# RF_Controller.net
KiCad netlist of a schematic drawn in Altium Designer
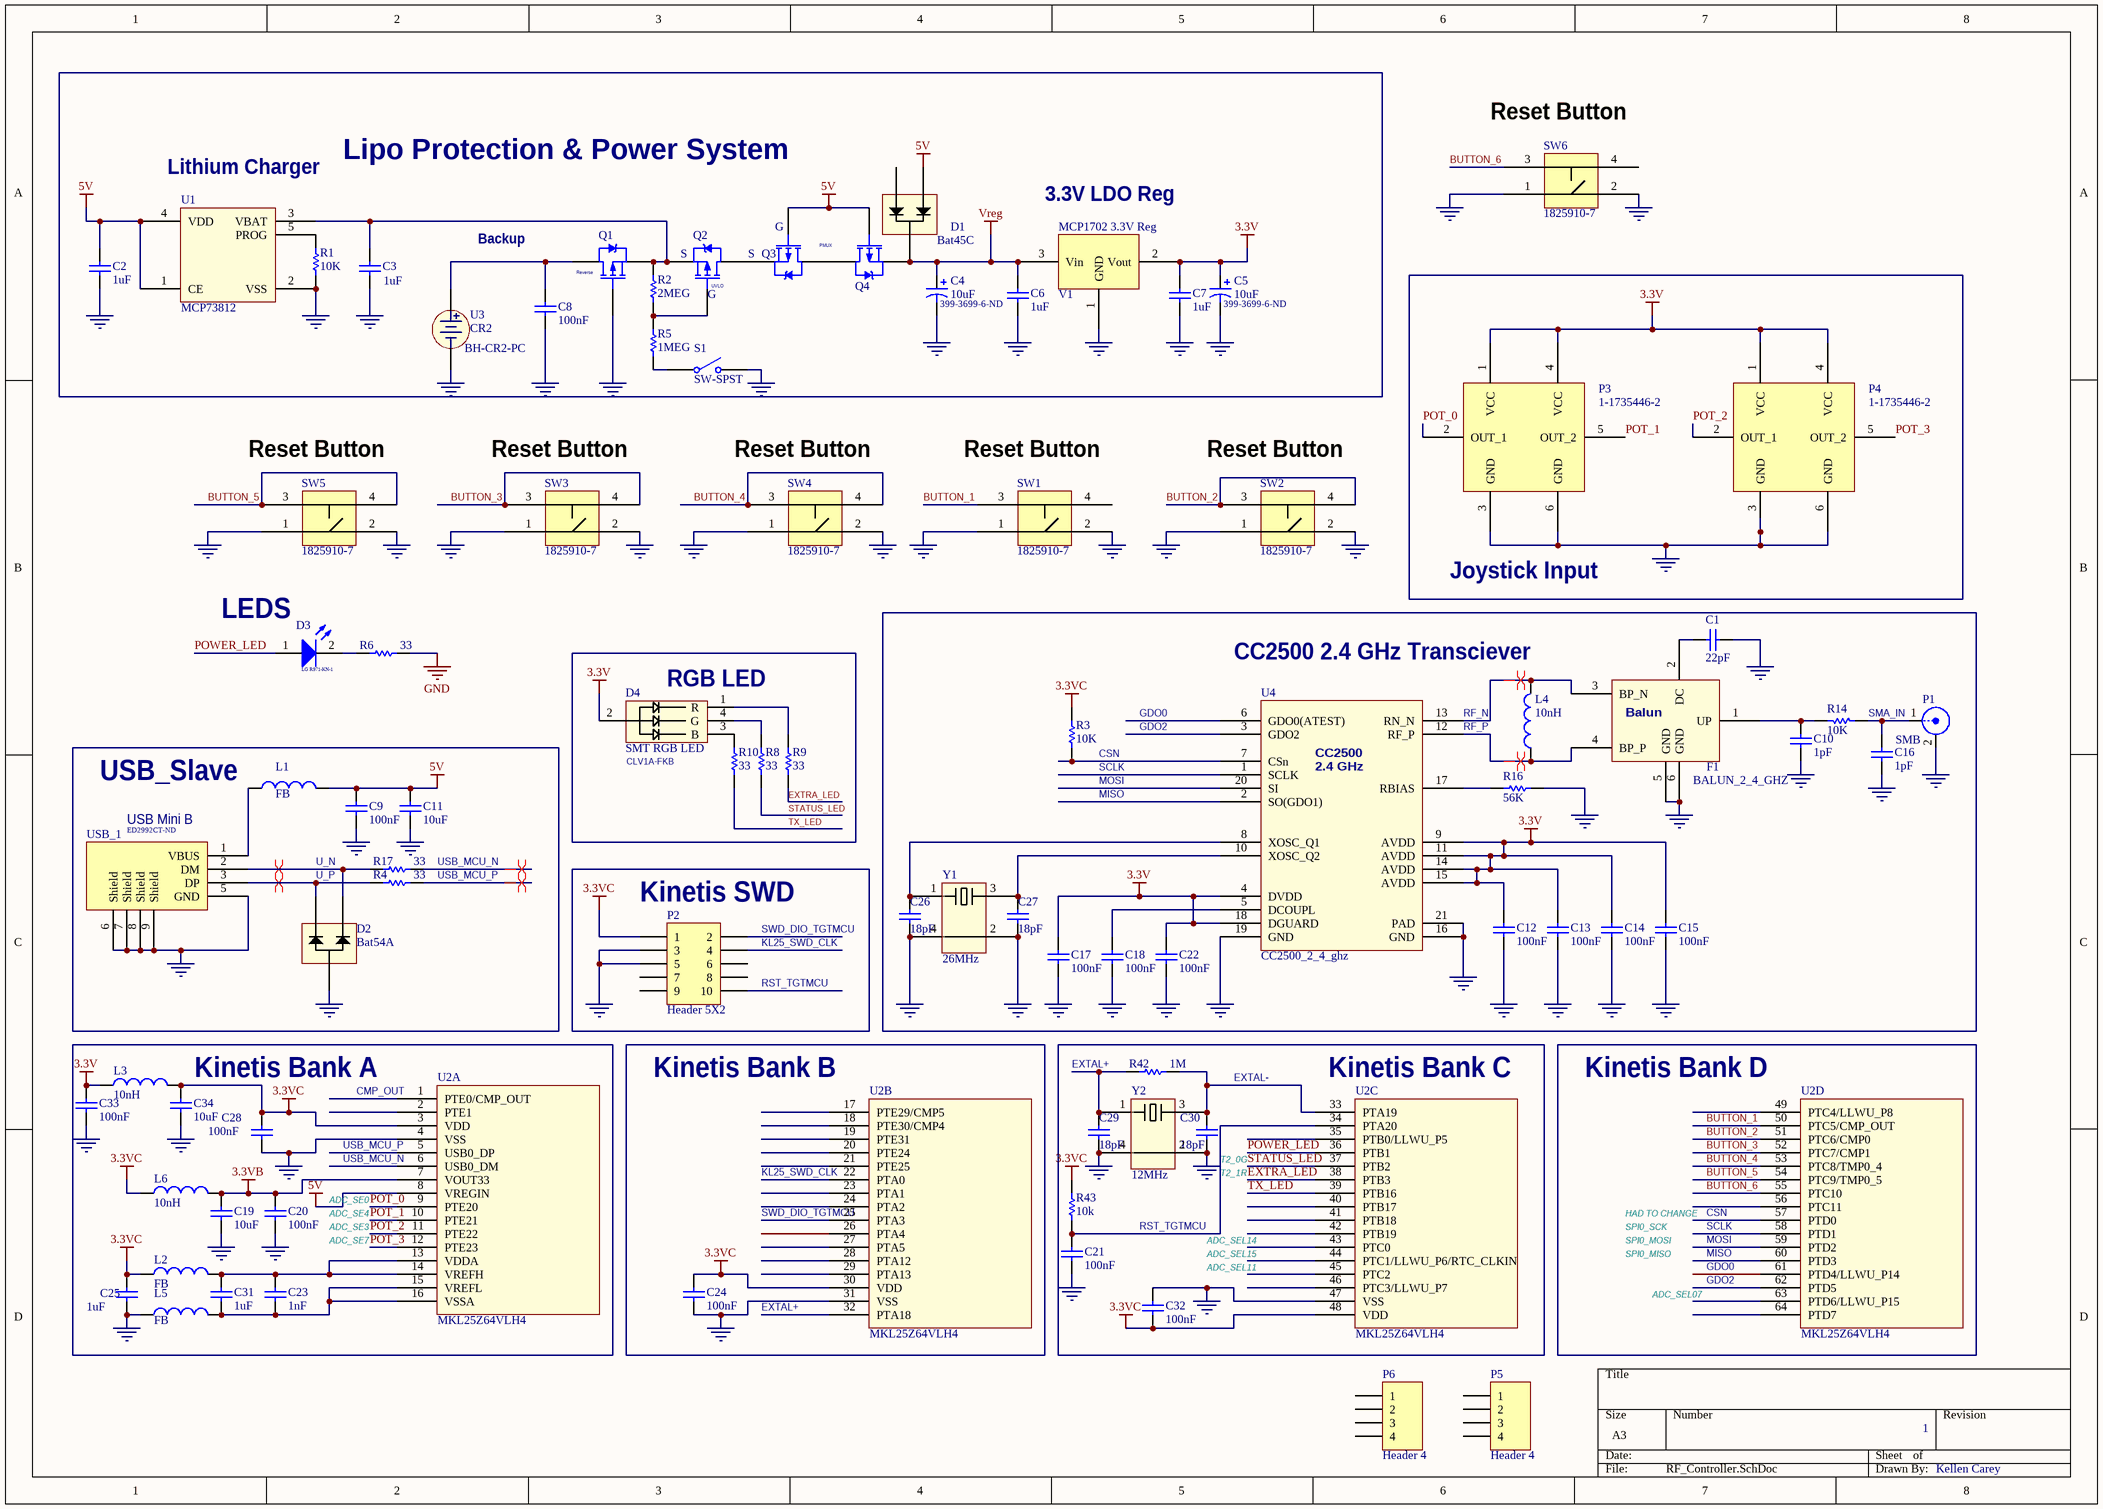
[diagram p0: RF_Controller.SchDoc]

(export (version "E")
  (design (tool "Eeschema 10.0.6"))
  (components
    (comp (ref "C1")
      (value "22pF")
      (footprint "1608[0603]C")
      (description "Capacitor (Semiconductor SIM Model)")
      (fields (field (name "Comment") "0805") (field (name "PUBLISHER") "Altium Limited"))
      (libsource (lib "Miscellaneous Devices") (part "Cap Semi"))
    )
    (comp (ref "C2")
      (value "1uF")
      (footprint "1608[0603]C")
      (description "Capacitor (Semiconductor SIM Model)")
      (fields (field (name "Comment") "0805") (field (name "PUBLISHER") "Altium Limited"))
      (libsource (lib "Miscellaneous Devices") (part "Cap Semi"))
    )
    (comp (ref "C3")
      (value "1uF")
      (footprint "1608[0603]C")
      (description "Capacitor (Semiconductor SIM Model)")
      (fields (field (name "Comment") "0805") (field (name "PUBLISHER") "Altium Limited"))
      (libsource (lib "Miscellaneous Devices") (part "Cap Semi"))
    )
    (comp (ref "C4")
      (value "10uF")
      (footprint "1206_C")
      (description "Polarized Capacitor (Radial)")
      (fields (field (name "ALTIUM_UNNAMED_1") "399-3699-6-ND") (field (name "Comment") "Cap Pol1"))
      (libsource (lib "Miscellaneous Devices") (part "Cap Pol1"))
    )
    (comp (ref "C5")
      (value "10uF")
      (footprint "1206_C")
      (description "Polarized Capacitor (Radial)")
      (fields (field (name "ALTIUM_UNNAMED_1") "399-3699-6-ND") (field (name "Comment") "Cap Pol1"))
      (libsource (lib "Miscellaneous Devices") (part "Cap Pol1"))
    )
    (comp (ref "C6")
      (value "1uF")
      (footprint "1608[0603]C")
      (description "Capacitor (Semiconductor SIM Model)")
      (fields (field (name "Comment") "0805") (field (name "PUBLISHER") "Altium Limited"))
      (libsource (lib "Miscellaneous Devices") (part "Cap Semi"))
    )
    (comp (ref "C7")
      (value "1uF")
      (footprint "1608[0603]C")
      (description "Capacitor (Semiconductor SIM Model)")
      (fields (field (name "Comment") "0805") (field (name "PUBLISHER") "Altium Limited"))
      (libsource (lib "Miscellaneous Devices") (part "Cap Semi"))
    )
    (comp (ref "C8")
      (value "100nF")
      (footprint "1608[0603]C")
      (description "Capacitor (Semiconductor SIM Model)")
      (fields (field (name "Comment") "0805") (field (name "PUBLISHER") "Altium Limited"))
      (libsource (lib "Miscellaneous Devices") (part "Cap Semi"))
    )
    (comp (ref "C9")
      (value "100nF")
      (footprint "1608[0603]C")
      (description "Capacitor (Semiconductor SIM Model)")
      (fields (field (name "Comment") "0805") (field (name "PUBLISHER") "Altium Limited"))
      (libsource (lib "Miscellaneous Devices") (part "Cap Semi"))
    )
    (comp (ref "C10")
      (value "1pF")
      (footprint "1608[0603]C")
      (description "Capacitor (Semiconductor SIM Model)")
      (fields (field (name "Comment") "0805") (field (name "PUBLISHER") "Altium Limited"))
      (libsource (lib "Miscellaneous Devices") (part "Cap Semi"))
    )
    (comp (ref "C11")
      (value "10uF")
      (footprint "C0805")
      (description "Capacitor (Semiconductor SIM Model)")
      (fields (field (name "Comment") "0805") (field (name "PUBLISHER") "Altium Limited"))
      (libsource (lib "Miscellaneous Devices") (part "Cap Semi"))
    )
    (comp (ref "C12")
      (value "100nF")
      (footprint "1608[0603]C")
      (description "Capacitor (Semiconductor SIM Model)")
      (fields (field (name "Comment") "0805") (field (name "PUBLISHER") "Altium Limited"))
      (libsource (lib "Miscellaneous Devices") (part "Cap Semi"))
    )
    (comp (ref "C13")
      (value "100nF")
      (footprint "1608[0603]C")
      (description "Capacitor (Semiconductor SIM Model)")
      (fields (field (name "Comment") "0805") (field (name "PUBLISHER") "Altium Limited"))
      (libsource (lib "Miscellaneous Devices") (part "Cap Semi"))
    )
    (comp (ref "C14")
      (value "100nF")
      (footprint "1608[0603]C")
      (description "Capacitor (Semiconductor SIM Model)")
      (fields (field (name "Comment") "0805") (field (name "PUBLISHER") "Altium Limited"))
      (libsource (lib "Miscellaneous Devices") (part "Cap Semi"))
    )
    (comp (ref "C15")
      (value "100nF")
      (footprint "1608[0603]C")
      (description "Capacitor (Semiconductor SIM Model)")
      (fields (field (name "Comment") "0805") (field (name "PUBLISHER") "Altium Limited"))
      (libsource (lib "Miscellaneous Devices") (part "Cap Semi"))
    )
    (comp (ref "C16")
      (value "1pF")
      (footprint "1608[0603]C")
      (description "Capacitor (Semiconductor SIM Model)")
      (fields (field (name "Comment") "0805") (field (name "PUBLISHER") "Altium Limited"))
      (libsource (lib "Miscellaneous Devices") (part "Cap Semi"))
    )
    (comp (ref "C17")
      (value "100nF")
      (footprint "1608[0603]C")
      (description "Capacitor (Semiconductor SIM Model)")
      (fields (field (name "Comment") "0805") (field (name "PUBLISHER") "Altium Limited"))
      (libsource (lib "Miscellaneous Devices") (part "Cap Semi"))
    )
    (comp (ref "C18")
      (value "100nF")
      (footprint "1608[0603]C")
      (description "Capacitor (Semiconductor SIM Model)")
      (fields (field (name "Comment") "0805") (field (name "PUBLISHER") "Altium Limited"))
      (libsource (lib "Miscellaneous Devices") (part "Cap Semi"))
    )
    (comp (ref "C19")
      (value "10uF")
      (footprint "C0805")
      (description "Capacitor (Semiconductor SIM Model)")
      (fields (field (name "Comment") "0805") (field (name "PUBLISHER") "Altium Limited"))
      (libsource (lib "Miscellaneous Devices") (part "Cap Semi"))
    )
    (comp (ref "C20")
      (value "100nF")
      (footprint "1608[0603]C")
      (description "Capacitor (Semiconductor SIM Model)")
      (fields (field (name "Comment") "0805") (field (name "PUBLISHER") "Altium Limited"))
      (libsource (lib "Miscellaneous Devices") (part "Cap Semi"))
    )
    (comp (ref "C21")
      (value "100nF")
      (footprint "1608[0603]C")
      (description "Capacitor (Semiconductor SIM Model)")
      (fields (field (name "Comment") "0805") (field (name "PUBLISHER") "Altium Limited"))
      (libsource (lib "Miscellaneous Devices") (part "Cap Semi"))
    )
    (comp (ref "C22")
      (value "100nF")
      (footprint "1608[0603]C")
      (description "Capacitor (Semiconductor SIM Model)")
      (fields (field (name "Comment") "0805") (field (name "PUBLISHER") "Altium Limited"))
      (libsource (lib "Miscellaneous Devices") (part "Cap Semi"))
    )
    (comp (ref "C23")
      (value "1nF")
      (footprint "1608[0603]C")
      (description "Capacitor (Semiconductor SIM Model)")
      (fields (field (name "Comment") "0805") (field (name "PUBLISHER") "Altium Limited"))
      (libsource (lib "Miscellaneous Devices") (part "Cap Semi"))
    )
    (comp (ref "C24")
      (value "100nF")
      (footprint "1608[0603]C")
      (description "Capacitor (Semiconductor SIM Model)")
      (fields (field (name "Comment") "0805") (field (name "PUBLISHER") "Altium Limited"))
      (libsource (lib "Miscellaneous Devices") (part "Cap Semi"))
    )
    (comp (ref "C25")
      (value "1uF")
      (footprint "1608[0603]C")
      (description "Capacitor (Semiconductor SIM Model)")
      (fields (field (name "Comment") "0805") (field (name "PUBLISHER") "Altium Limited"))
      (libsource (lib "Miscellaneous Devices") (part "Cap Semi"))
    )
    (comp (ref "C26")
      (value "18pF")
      (footprint "1608[0603]C")
      (description "Capacitor (Semiconductor SIM Model)")
      (fields (field (name "PART_NUMBER") "CL10C180JC8NNNC") (field (name "Comment") "0805"))
      (libsource (lib "Miscellaneous Devices") (part "Cap Semi"))
    )
    (comp (ref "C27")
      (value "18pF")
      (footprint "1608[0603]C")
      (description "Capacitor (Semiconductor SIM Model)")
      (fields (field (name "PART_NUMBER") "CL10C180JC8NNNC") (field (name "Comment") "0805"))
      (libsource (lib "Miscellaneous Devices") (part "Cap Semi"))
    )
    (comp (ref "C28")
      (value "100nF")
      (footprint "1608[0603]C")
      (description "Capacitor (Semiconductor SIM Model)")
      (fields (field (name "Comment") "0805") (field (name "PUBLISHER") "Altium Limited"))
      (libsource (lib "Miscellaneous Devices") (part "Cap Semi"))
    )
    (comp (ref "C29")
      (value "18pF")
      (footprint "1608[0603]C")
      (description "Capacitor (Semiconductor SIM Model)")
      (fields (field (name "Comment") "0805") (field (name "PUBLISHER") "Altium Limited"))
      (libsource (lib "Miscellaneous Devices") (part "Cap Semi"))
    )
    (comp (ref "C30")
      (value "18pF")
      (footprint "1608[0603]C")
      (description "Capacitor (Semiconductor SIM Model)")
      (fields (field (name "Comment") "0805") (field (name "PUBLISHER") "Altium Limited"))
      (libsource (lib "Miscellaneous Devices") (part "Cap Semi"))
    )
    (comp (ref "C31")
      (value "1uF")
      (footprint "1608[0603]C")
      (description "Capacitor (Semiconductor SIM Model)")
      (fields (field (name "Comment") "0805") (field (name "PUBLISHER") "Altium Limited"))
      (libsource (lib "Miscellaneous Devices") (part "Cap Semi"))
    )
    (comp (ref "C32")
      (value "100nF")
      (footprint "1608[0603]C")
      (description "Capacitor (Semiconductor SIM Model)")
      (fields (field (name "Comment") "0805") (field (name "PUBLISHER") "Altium Limited"))
      (libsource (lib "Miscellaneous Devices") (part "Cap Semi"))
    )
    (comp (ref "C33")
      (value "100nF")
      (footprint "1608[0603]C")
      (description "Capacitor (Semiconductor SIM Model)")
      (fields (field (name "Comment") "0805") (field (name "PUBLISHER") "Altium Limited"))
      (libsource (lib "Miscellaneous Devices") (part "Cap Semi"))
    )
    (comp (ref "C34")
      (value "10uF")
      (footprint "C0805")
      (description "Capacitor (Semiconductor SIM Model)")
      (fields (field (name "Comment") "0805") (field (name "PUBLISHER") "Altium Limited"))
      (libsource (lib "Miscellaneous Devices") (part "Cap Semi"))
    )
    (comp (ref "D1") (value "Bat45C") (footprint "SOT-23B_N") (libsource (lib "bat45") (part "Bat45C")))
    (comp (ref "D2")
      (value "Bat54A")
      (footprint "SOT-23B_N")
      (description "Bat45C")
      (libsource (lib "GSOT05CGS08") (part "Bat45C"))
    )
    (comp (ref "D3")
      (value "LG R971-KN-1")
      (footprint "6-0805_M_LED_LIB")
      (libsource (lib "Miscellaneous Devices") (part "LED3"))
    )
    (comp (ref "D4")
      (value "SMT RGB LED")
      (footprint "CLV1A-FKB_RGB_3D")
      (fields (field (name "ALTIUM_UNNAMED_1") "CLV1A-FKB"))
      (libsource (lib "RGB_LED") (part "RGB_LED_SMT"))
    )
    (comp (ref "F1")
      (value "BALUN_2_4_GHZ")
      (footprint "Balun")
      (description "2450BM15B0003")
      (libsource (lib "2450BM15B0003") (part "BALUN_2_4_GHZ"))
    )
    (comp (ref "L1")
      (value "FB")
      (footprint "1608[0603]R")
      (description "Inductor")
      (libsource (lib "Miscellaneous Devices") (part "Inductor"))
    )
    (comp (ref "L2")
      (value "FB")
      (footprint "1608[0603]R")
      (description "Inductor")
      (libsource (lib "Miscellaneous Devices") (part "Inductor"))
    )
    (comp (ref "L3")
      (value "10nH")
      (footprint "1608[0603]R")
      (description "Inductor")
      (libsource (lib "Miscellaneous Devices") (part "Inductor"))
    )
    (comp (ref "L4")
      (value "10nH")
      (footprint "1608[0603]R")
      (description "Inductor")
      (libsource (lib "Miscellaneous Devices") (part "Inductor"))
    )
    (comp (ref "L5")
      (value "FB")
      (footprint "1608[0603]R")
      (description "Inductor")
      (libsource (lib "Miscellaneous Devices") (part "Inductor"))
    )
    (comp (ref "L6")
      (value "10nH")
      (footprint "1608[0603]R")
      (description "Inductor")
      (libsource (lib "Miscellaneous Devices") (part "Inductor"))
    )
    (comp (ref "P1")
      (value "SMB")
      (footprint "SMA")
      (description "SMB Straight Connector")
      (fields (field (name "PART #") "5-1814832-1"))
      (libsource (lib "Miscellaneous Connectors") (part "SMB"))
    )
    (comp (ref "P2")
      (value "Header 5X2")
      (footprint "MHDR2X5")
      (description "Header, 5-Pin, Dual row")
      (fields (field (name "PUBLISHER") "Altium Limited"))
      (libsource (lib "Miscellaneous Connectors") (part "Header 5X2"))
    )
    (comp (ref "P3")
      (value "1-1735446-2")
      (footprint "1-1735446-2")
      (description "TE Connectivity AMP Connector")
      (libsource (lib "Joystick") (part "TE_CONN"))
    )
    (comp (ref "P4")
      (value "1-1735446-2")
      (footprint "1-1735446-2")
      (description "TE Connectivity AMP Connector")
      (libsource (lib "Joystick") (part "TE_CONN"))
    )
    (comp (ref "P5")
      (value "Header 4")
      (footprint "Joystick_Mechanical_Footprint_2")
      (description "Header, 4-Pin")
      (fields (field (name "PUBLISHER") "Altium Limited"))
      (libsource (lib "Miscellaneous Connectors") (part "Header 4"))
    )
    (comp (ref "P6")
      (value "Header 4")
      (footprint "Joystick_Mechanical_Footprint_2")
      (description "Header, 4-Pin")
      (fields (field (name "PUBLISHER") "Altium Limited"))
      (libsource (lib "Miscellaneous Connectors") (part "Header 4"))
    )
    (comp (ref "Q1")
      (value "k")
      (footprint "SOT-23_L")
      (description "P-Channel Power MOSFET")
      (libsource (lib "Miscellaneous Devices") (part "PMOS-2"))
    )
    (comp (ref "Q2")
      (value "k")
      (footprint "SOT-23_L")
      (description "P-Channel Power MOSFET")
      (libsource (lib "Miscellaneous Devices") (part "PMOS-2"))
    )
    (comp (ref "Q3")
      (value "k")
      (footprint "SOT-23_L")
      (description "P-Channel Power MOSFET")
      (libsource (lib "Miscellaneous Devices") (part "PMOS-2"))
    )
    (comp (ref "Q4")
      (value "k")
      (footprint "SOT-23_L")
      (description "P-Channel Power MOSFET")
      (libsource (lib "Miscellaneous Devices") (part "PMOS-2"))
    )
    (comp (ref "R1")
      (value "10K")
      (footprint "1608[0603]R")
      (description "Resistor")
      (fields (field (name "Comment") "Res1") (field (name "PUBLISHER") "Altium Limited"))
      (libsource (lib "Miscellaneous Devices") (part "Res1"))
    )
    (comp (ref "R2")
      (value "2MEG")
      (footprint "1608[0603]R")
      (description "Resistor")
      (fields (field (name "Comment") "Res1") (field (name "PUBLISHER") "Altium Limited"))
      (libsource (lib "Miscellaneous Devices") (part "Res1"))
    )
    (comp (ref "R3")
      (value "10K")
      (footprint "1608[0603]R")
      (description "Resistor")
      (fields (field (name "Comment") "Res1") (field (name "PUBLISHER") "Altium Limited"))
      (libsource (lib "Miscellaneous Devices") (part "Res1"))
    )
    (comp (ref "R4")
      (value "33")
      (footprint "1608[0603]R")
      (description "Resistor")
      (fields (field (name "Comment") "Res1") (field (name "PUBLISHER") "Altium Limited"))
      (libsource (lib "Miscellaneous Devices") (part "Res1"))
    )
    (comp (ref "R5")
      (value "1MEG")
      (footprint "1608[0603]R")
      (description "Resistor")
      (fields (field (name "Comment") "Res1") (field (name "PUBLISHER") "Altium Limited"))
      (libsource (lib "Miscellaneous Devices") (part "Res1"))
    )
    (comp (ref "R6")
      (value "33")
      (footprint "1608[0603]R")
      (description "Resistor")
      (fields (field (name "Comment") "Res1") (field (name "PUBLISHER") "Altium Limited"))
      (libsource (lib "Miscellaneous Devices") (part "Res1"))
    )
    (comp (ref "R8")
      (value "33")
      (footprint "1608[0603]R")
      (description "Resistor")
      (fields (field (name "Comment") "Res1") (field (name "PUBLISHER") "Altium Limited"))
      (libsource (lib "Miscellaneous Devices") (part "Res1"))
    )
    (comp (ref "R9")
      (value "33")
      (footprint "1608[0603]R")
      (description "Resistor")
      (fields (field (name "Comment") "Res1") (field (name "PUBLISHER") "Altium Limited"))
      (libsource (lib "Miscellaneous Devices") (part "Res1"))
    )
    (comp (ref "R10")
      (value "33")
      (footprint "1608[0603]R")
      (description "Resistor")
      (fields (field (name "Comment") "Res1") (field (name "PUBLISHER") "Altium Limited"))
      (libsource (lib "Miscellaneous Devices") (part "Res1"))
    )
    (comp (ref "R14")
      (value "10K")
      (footprint "1608[0603]R")
      (description "Resistor")
      (fields (field (name "Comment") "Res1") (field (name "PUBLISHER") "Altium Limited"))
      (libsource (lib "Miscellaneous Devices") (part "Res1"))
    )
    (comp (ref "R16")
      (value "56K")
      (footprint "1608[0603]R")
      (description "Resistor")
      (fields (field (name "Comment") "Res1") (field (name "PUBLISHER") "Altium Limited"))
      (libsource (lib "Miscellaneous Devices") (part "Res1"))
    )
    (comp (ref "R17")
      (value "33")
      (footprint "1608[0603]R")
      (description "Resistor")
      (fields (field (name "Comment") "Res1") (field (name "PUBLISHER") "Altium Limited"))
      (libsource (lib "Miscellaneous Devices") (part "Res1"))
    )
    (comp (ref "R42")
      (value "1M")
      (footprint "1608[0603]R")
      (description "Resistor")
      (fields (field (name "Comment") "Res1") (field (name "PUBLISHER") "Altium Limited"))
      (libsource (lib "Miscellaneous Devices") (part "Res1"))
    )
    (comp (ref "R43")
      (value "10k")
      (footprint "1608[0603]R")
      (description "Resistor")
      (fields (field (name "Comment") "Res1") (field (name "PUBLISHER") "Altium Limited"))
      (libsource (lib "Miscellaneous Devices") (part "Res1"))
    )
    (comp (ref "S1")
      (value "SW-SPST")
      (footprint "418117270901_ft_prt_3d")
      (description "Single-Pole, Single-Throw Switch")
      (fields (field (name "PART #") "418117270901"))
      (libsource (lib "Miscellaneous Devices") (part "SW-SPST"))
    )
    (comp (ref "SW1")
      (value "1825910-7")
      (footprint "Tact_ButtonVV")
      (libsource (lib "Buttons") (part "D6x-XX"))
    )
    (comp (ref "SW2")
      (value "1825910-7")
      (footprint "Tact_ButtonVV")
      (libsource (lib "Buttons") (part "D6x-XX"))
    )
    (comp (ref "SW3")
      (value "1825910-7")
      (footprint "Tact_ButtonVV")
      (libsource (lib "Buttons") (part "D6x-XX"))
    )
    (comp (ref "SW4")
      (value "1825910-7")
      (footprint "Tact_ButtonVV")
      (libsource (lib "Buttons") (part "D6x-XX"))
    )
    (comp (ref "SW5")
      (value "1825910-7")
      (footprint "Tact_ButtonVV")
      (libsource (lib "Buttons") (part "D6x-XX"))
    )
    (comp (ref "SW6")
      (value "1825910-7")
      (footprint "Tact_ButtonVV")
      (libsource (lib "Buttons") (part "D6x-XX"))
    )
    (comp (ref "U1") (value "MCP73812") (footprint "SOT23-5AL") (libsource (lib "MCP7381") (part "MCP73812")))
    (comp (ref "U2")
      (value "MKL25Z64VLH4")
      (footprint "TSQFP50P1200X1200-64M")
      (description "MKL25Z64VLH4 MCU")
      (libsource (lib "MKL25Z64VLH4") (part "MKL25Z64VLH4"))
    )
    (comp (ref "U3")
      (value "CR2")
      (footprint "BH-CR2-PC_FTPRT")
      (fields (field (name "ALTIUM_UNNAMED_1") "BH-CR2-PC"))
      (libsource (lib "lithium_bat") (part "CR2"))
    )
    (comp (ref "U4")
      (value "CC2500_2_4_ghz")
      (footprint "QFN50P400X400-20VM")
      (libsource (lib "CC2500") (part "CC2500_2_4_ghz"))
    )
    (comp (ref "USB_1")
      (value "USB-M2xFxx")
      (footprint "USB_Mini_B_SMT")
      (description "USB Mini-B for USB-M2xFxx")
      (fields (field (name "DIGIKEY") "ED2992CT-ND"))
      (libsource (lib "USB-M2xFxx") (part "USB-M2xFxx"))
    )
    (comp (ref "V1")
      (value "MCP1702 3.3V Reg")
      (footprint "SOT-23B_M")
      (description "MCP1700 3.3V REG")
      (libsource (lib "MCP1700") (part "MCP1700"))
    )
    (comp (ref "Y1")
      (value "26MHz")
      (footprint "7M-12.000MAAJ-T_FP")
      (description "12MHz Micro Crystal")
      (libsource (lib "12MHz_micro_crystal") (part "12MHz_Crystal"))
    )
    (comp (ref "Y2")
      (value "12MHz")
      (footprint "7M-12.000MAAJ-T_FP")
      (description "12MHz Micro Crystal")
      (libsource (lib "12MHz_micro_crystal") (part "12MHz_Crystal"))
    )
  )
  (nets
    (net (code "1") (name "/BUTTON_1") (class "Default")
      (node (ref "SW1") (pin "3") (pintype "passive"))
      (node (ref "U2") (pin "50") (pinfunction "PTC5/CMP_OUT_50") (pintype "passive"))
    )
    (net (code "2") (name "/BUTTON_2") (class "Default")
      (node (ref "SW2") (pin "3") (pintype "passive"))
      (node (ref "SW2") (pin "4") (pintype "passive"))
      (node (ref "U2") (pin "51") (pinfunction "PTC6/CMP0_51") (pintype "passive"))
    )
    (net (code "3") (name "/BUTTON_3") (class "Default")
      (node (ref "SW3") (pin "3") (pintype "passive"))
      (node (ref "SW3") (pin "4") (pintype "passive"))
      (node (ref "U2") (pin "52") (pinfunction "PTC7/CMP1_52") (pintype "passive"))
    )
    (net (code "4") (name "/BUTTON_4") (class "Default")
      (node (ref "SW4") (pin "3") (pintype "passive"))
      (node (ref "SW4") (pin "4") (pintype "passive"))
      (node (ref "U2") (pin "53") (pinfunction "PTC8/TMP0_4_53") (pintype "passive"))
    )
    (net (code "5") (name "/BUTTON_5") (class "Default")
      (node (ref "SW5") (pin "3") (pintype "passive"))
      (node (ref "SW5") (pin "4") (pintype "passive"))
      (node (ref "U2") (pin "54") (pinfunction "PTC9/TMP0_5_54") (pintype "passive"))
    )
    (net (code "6") (name "/BUTTON_6") (class "Default")
      (node (ref "SW6") (pin "3") (pintype "passive"))
      (node (ref "U2") (pin "55") (pinfunction "PTC10_55") (pintype "passive"))
    )
    (net (code "7") (name "/CMP_OUT") (class "Default")
      (node (ref "U2") (pin "1") (pinfunction "PTE0_1") (pintype "passive"))
    )
    (net (code "8") (name "/CSN") (class "Default")
      (node (ref "R3") (pin "1") (pinfunction "1_1") (pintype "passive"))
      (node (ref "U2") (pin "57") (pinfunction "PTD0_57") (pintype "passive"))
      (node (ref "U4") (pin "7") (pinfunction "CSn_7") (pintype "passive"))
    )
    (net (code "9") (name "/EXTAL+") (class "Default")
      (node (ref "C29") (pin "2") (pinfunction "2_2") (pintype "passive"))
      (node (ref "R42") (pin "1") (pinfunction "1_1") (pintype "passive"))
      (node (ref "U2") (pin "32") (pinfunction "PTA18_32") (pintype "passive"))
      (node (ref "Y2") (pin "1") (pinfunction "X1_1") (pintype "passive"))
    )
    (net (code "10") (name "/EXTAL-") (class "Default")
      (node (ref "C30") (pin "2") (pinfunction "2_2") (pintype "passive"))
      (node (ref "R42") (pin "2") (pinfunction "2_2") (pintype "passive"))
      (node (ref "U2") (pin "33") (pinfunction "PTA19_33") (pintype "passive"))
      (node (ref "Y2") (pin "3") (pinfunction "X2_3") (pintype "passive"))
    )
    (net (code "11") (name "/EXTRA_LED") (class "Default")
      (node (ref "R9") (pin "1") (pinfunction "1_1") (pintype "passive"))
      (node (ref "U2") (pin "38") (pinfunction "PTB3_38") (pintype "passive"))
    )
    (net (code "12") (name "/GDO0") (class "Default")
      (node (ref "U2") (pin "61") (pinfunction "PTD4/LLWU_P14_61") (pintype "passive"))
      (node (ref "U4") (pin "6") (pinfunction "GDO0(ATEST)_6") (pintype "passive"))
    )
    (net (code "13") (name "/GDO2") (class "Default")
      (node (ref "U2") (pin "62") (pinfunction "PTD5_62") (pintype "passive"))
      (node (ref "U4") (pin "3") (pinfunction "GDO2_3") (pintype "passive"))
    )
    (net (code "14") (name "/KL25_SWD_CLK") (class "Default")
      (node (ref "P2") (pin "4") (pinfunction "4_4") (pintype "passive"))
      (node (ref "U2") (pin "22") (pinfunction "PTA0_22") (pintype "passive"))
    )
    (net (code "15") (name "/MISO") (class "Default")
      (node (ref "U2") (pin "60") (pinfunction "PTD3_60") (pintype "passive"))
      (node (ref "U4") (pin "2") (pinfunction "SO(GDO1)_2") (pintype "passive"))
    )
    (net (code "16") (name "/MOSI") (class "Default")
      (node (ref "U2") (pin "59") (pinfunction "PTD2_59") (pintype "passive"))
      (node (ref "U4") (pin "20") (pinfunction "SI_20") (pintype "passive"))
    )
    (net (code "17") (name "/POT_0") (class "Default")
      (node (ref "P3") (pin "2") (pinfunction "OUT_1_2") (pintype "passive"))
      (node (ref "U2") (pin "9") (pinfunction "PTE20_9") (pintype "passive"))
    )
    (net (code "18") (name "/POT_1") (class "Default")
      (node (ref "P3") (pin "5") (pinfunction "OUT_2_5") (pintype "passive"))
      (node (ref "U2") (pin "10") (pinfunction "PTE21_10") (pintype "passive"))
    )
    (net (code "19") (name "/POT_2") (class "Default")
      (node (ref "P4") (pin "2") (pinfunction "OUT_1_2") (pintype "passive"))
      (node (ref "U2") (pin "11") (pinfunction "PTE22_11") (pintype "passive"))
    )
    (net (code "20") (name "/POT_3") (class "Default")
      (node (ref "P4") (pin "5") (pinfunction "OUT_2_5") (pintype "passive"))
      (node (ref "U2") (pin "12") (pinfunction "PTE23_12") (pintype "passive"))
    )
    (net (code "21") (name "/POWER_LED") (class "Default")
      (node (ref "D3") (pin "1") (pinfunction "A_1") (pintype "passive"))
      (node (ref "U2") (pin "36") (pinfunction "PTB1_36") (pintype "passive"))
    )
    (net (code "22") (name "/RF_N") (class "Default")
      (node (ref "F1") (pin "3") (pinfunction "BP_N_3") (pintype "passive"))
      (node (ref "L4") (pin "1") (pinfunction "1_1") (pintype "passive"))
      (node (ref "U4") (pin "13") (pinfunction "RN_N_13") (pintype "passive"))
    )
    (net (code "23") (name "/RF_P") (class "Default")
      (node (ref "F1") (pin "4") (pinfunction "BP_P_4") (pintype "passive"))
      (node (ref "L4") (pin "2") (pinfunction "2_2") (pintype "passive"))
      (node (ref "U4") (pin "12") (pinfunction "RF_P_12") (pintype "passive"))
    )
    (net (code "24") (name "/RST_TGTMCU") (class "Default")
      (node (ref "C21") (pin "2") (pinfunction "2_2") (pintype "passive"))
      (node (ref "P2") (pin "10") (pinfunction "10_10") (pintype "passive"))
      (node (ref "R43") (pin "1") (pinfunction "1_1") (pintype "passive"))
      (node (ref "U2") (pin "34") (pinfunction "PTA20_34") (pintype "passive"))
    )
    (net (code "25") (name "/SCLK") (class "Default")
      (node (ref "U2") (pin "58") (pinfunction "PTD1_58") (pintype "passive"))
      (node (ref "U4") (pin "1") (pinfunction "SCLK_1") (pintype "passive"))
    )
    (net (code "26") (name "/SMA_IN") (class "Default")
      (node (ref "C16") (pin "2") (pinfunction "2_2") (pintype "passive"))
      (node (ref "P1") (pin "1") (pinfunction "X_1") (pintype "passive"))
      (node (ref "R14") (pin "1") (pinfunction "1_1") (pintype "passive"))
    )
    (net (code "27") (name "/STATUS_LED") (class "Default")
      (node (ref "R8") (pin "1") (pinfunction "1_1") (pintype "passive"))
      (node (ref "U2") (pin "37") (pinfunction "PTB2_37") (pintype "passive"))
    )
    (net (code "28") (name "/SWD_DIO_TGTMCU") (class "Default")
      (node (ref "P2") (pin "2") (pinfunction "2_2") (pintype "passive"))
      (node (ref "U2") (pin "25") (pinfunction "PTA3_25") (pintype "passive"))
    )
    (net (code "29") (name "/TX_LED") (class "Default")
      (node (ref "R10") (pin "1") (pinfunction "1_1") (pintype "passive"))
      (node (ref "U2") (pin "39") (pinfunction "PTB16_39") (pintype "passive"))
    )
    (net (code "30") (name "/USB_MCU_N") (class "Default")
      (node (ref "R17") (pin "2") (pinfunction "2_2") (pintype "passive"))
      (node (ref "U2") (pin "6") (pinfunction "USB0_DM_6") (pintype "passive"))
    )
    (net (code "31") (name "/USB_MCU_P") (class "Default")
      (node (ref "R4") (pin "2") (pinfunction "2_2") (pintype "passive"))
      (node (ref "U2") (pin "5") (pinfunction "USB0_DP_5") (pintype "passive"))
    )
    (net (code "32") (name "/U_N") (class "Default")
      (node (ref "D2") (pin "1") (pinfunction "0_1") (pintype "passive"))
      (node (ref "R17") (pin "1") (pinfunction "1_1") (pintype "passive"))
      (node (ref "USB_1") (pin "2") (pinfunction "DM_2") (pintype "passive"))
    )
    (net (code "33") (name "/U_P") (class "Default")
      (node (ref "D2") (pin "2") (pinfunction "0_2") (pintype "passive"))
      (node (ref "R4") (pin "1") (pinfunction "1_1") (pintype "passive"))
      (node (ref "USB_1") (pin "3") (pinfunction "DP_3") (pintype "passive"))
    )
    (net (code "34") (name "3.3V") (class "Default")
      (node (ref "C12") (pin "1") (pinfunction "1_1") (pintype "passive"))
      (node (ref "C13") (pin "1") (pinfunction "1_1") (pintype "passive"))
      (node (ref "C14") (pin "1") (pinfunction "1_1") (pintype "passive"))
      (node (ref "C15") (pin "1") (pinfunction "1_1") (pintype "passive"))
      (node (ref "C17") (pin "1") (pinfunction "1_1") (pintype "passive"))
      (node (ref "C22") (pin "1") (pinfunction "1_1") (pintype "passive"))
      (node (ref "C33") (pin "1") (pinfunction "1_1") (pintype "passive"))
      (node (ref "C5") (pin "1") (pinfunction "1_1") (pintype "passive"))
      (node (ref "C7") (pin "1") (pinfunction "1_1") (pintype "passive"))
      (node (ref "D4") (pin "2") (pinfunction "V+_2") (pintype "passive"))
      (node (ref "L3") (pin "2") (pinfunction "2_2") (pintype "passive"))
      (node (ref "P3") (pin "1") (pinfunction "VCC_1") (pintype "power_in"))
      (node (ref "P3") (pin "4") (pinfunction "VCC_4") (pintype "power_in"))
      (node (ref "P4") (pin "1") (pinfunction "VCC_1") (pintype "power_in"))
      (node (ref "P4") (pin "4") (pinfunction "VCC_4") (pintype "power_in"))
      (node (ref "U4") (pin "11") (pinfunction "AVDD_11") (pintype "passive"))
      (node (ref "U4") (pin "14") (pinfunction "AVDD_14") (pintype "passive"))
      (node (ref "U4") (pin "15") (pinfunction "AVDD_15") (pintype "passive"))
      (node (ref "U4") (pin "18") (pinfunction "DGUARD_18") (pintype "passive"))
      (node (ref "U4") (pin "4") (pinfunction "DVDD_4") (pintype "passive"))
      (node (ref "U4") (pin "9") (pinfunction "AVDD_9") (pintype "passive"))
      (node (ref "V1") (pin "2") (pinfunction "Vout_2") (pintype "passive"))
    )
    (net (code "35") (name "3.3VB") (class "Default")
      (node (ref "C19") (pin "1") (pinfunction "1_1") (pintype "passive"))
      (node (ref "C20") (pin "1") (pinfunction "1_1") (pintype "passive"))
      (node (ref "L6") (pin "1") (pinfunction "1_1") (pintype "passive"))
      (node (ref "U2") (pin "7") (pinfunction "VOUT33_7") (pintype "passive"))
    )
    (net (code "36") (name "3.3VC") (class "Default")
      (node (ref "C24") (pin "2") (pinfunction "2_2") (pintype "passive"))
      (node (ref "C25") (pin "2") (pinfunction "2_2") (pintype "passive"))
      (node (ref "C28") (pin "2") (pinfunction "2_2") (pintype "passive"))
      (node (ref "C32") (pin "1") (pinfunction "1_1") (pintype "passive"))
      (node (ref "C34") (pin "1") (pinfunction "1_1") (pintype "passive"))
      (node (ref "L2") (pin "2") (pinfunction "2_2") (pintype "passive"))
      (node (ref "L3") (pin "1") (pinfunction "1_1") (pintype "passive"))
      (node (ref "L6") (pin "2") (pinfunction "2_2") (pintype "passive"))
      (node (ref "P2") (pin "1") (pinfunction "1_1") (pintype "passive"))
      (node (ref "R3") (pin "2") (pinfunction "2_2") (pintype "passive"))
      (node (ref "R43") (pin "2") (pinfunction "2_2") (pintype "passive"))
      (node (ref "U2") (pin "3") (pinfunction "VDD_3") (pintype "passive"))
      (node (ref "U2") (pin "30") (pinfunction "VDD_30") (pintype "passive"))
      (node (ref "U2") (pin "48") (pinfunction "VDD_48") (pintype "passive"))
    )
    (net (code "37") (name "5V") (class "Default")
      (node (ref "C11") (pin "1") (pinfunction "1_1") (pintype "passive"))
      (node (ref "C2") (pin "1") (pinfunction "1_1") (pintype "passive"))
      (node (ref "C9") (pin "1") (pinfunction "1_1") (pintype "passive"))
      (node (ref "D1") (pin "1") (pinfunction "0_1") (pintype "passive"))
      (node (ref "L1") (pin "1") (pinfunction "1_1") (pintype "passive"))
      (node (ref "Q3") (pin "1") (pinfunction "G_1") (pintype "passive"))
      (node (ref "Q4") (pin "1") (pinfunction "G_1") (pintype "passive"))
      (node (ref "U1") (pin "1") (pinfunction "CE_1") (pintype "passive"))
      (node (ref "U1") (pin "4") (pinfunction "VDD_4") (pintype "passive"))
      (node (ref "U2") (pin "8") (pinfunction "VREGIN_8") (pintype "passive"))
    )
    (net (code "38") (name "GND") (class "Default")
      (node (ref "C1") (pin "2") (pinfunction "2_2") (pintype "passive"))
      (node (ref "C10") (pin "1") (pinfunction "1_1") (pintype "passive"))
      (node (ref "C11") (pin "2") (pinfunction "2_2") (pintype "passive"))
      (node (ref "C12") (pin "2") (pinfunction "2_2") (pintype "passive"))
      (node (ref "C13") (pin "2") (pinfunction "2_2") (pintype "passive"))
      (node (ref "C14") (pin "2") (pinfunction "2_2") (pintype "passive"))
      (node (ref "C15") (pin "2") (pinfunction "2_2") (pintype "passive"))
      (node (ref "C16") (pin "1") (pinfunction "1_1") (pintype "passive"))
      (node (ref "C17") (pin "2") (pinfunction "2_2") (pintype "passive"))
      (node (ref "C18") (pin "2") (pinfunction "2_2") (pintype "passive"))
      (node (ref "C19") (pin "2") (pinfunction "2_2") (pintype "passive"))
      (node (ref "C2") (pin "2") (pinfunction "2_2") (pintype "passive"))
      (node (ref "C20") (pin "2") (pinfunction "2_2") (pintype "passive"))
      (node (ref "C21") (pin "1") (pinfunction "1_1") (pintype "passive"))
      (node (ref "C22") (pin "2") (pinfunction "2_2") (pintype "passive"))
      (node (ref "C24") (pin "1") (pinfunction "1_1") (pintype "passive"))
      (node (ref "C25") (pin "1") (pinfunction "1_1") (pintype "passive"))
      (node (ref "C26") (pin "1") (pinfunction "1_1") (pintype "passive"))
      (node (ref "C27") (pin "1") (pinfunction "1_1") (pintype "passive"))
      (node (ref "C28") (pin "1") (pinfunction "1_1") (pintype "passive"))
      (node (ref "C29") (pin "1") (pinfunction "1_1") (pintype "passive"))
      (node (ref "C3") (pin "2") (pinfunction "2_2") (pintype "passive"))
      (node (ref "C30") (pin "1") (pinfunction "1_1") (pintype "passive"))
      (node (ref "C32") (pin "2") (pinfunction "2_2") (pintype "passive"))
      (node (ref "C33") (pin "2") (pinfunction "2_2") (pintype "passive"))
      (node (ref "C34") (pin "2") (pinfunction "2_2") (pintype "passive"))
      (node (ref "C4") (pin "2") (pinfunction "2_2") (pintype "passive"))
      (node (ref "C5") (pin "2") (pinfunction "2_2") (pintype "passive"))
      (node (ref "C6") (pin "2") (pinfunction "2_2") (pintype "passive"))
      (node (ref "C7") (pin "2") (pinfunction "2_2") (pintype "passive"))
      (node (ref "C8") (pin "2") (pinfunction "2_2") (pintype "passive"))
      (node (ref "C9") (pin "2") (pinfunction "2_2") (pintype "passive"))
      (node (ref "D2") (pin "3") (pinfunction "0_3") (pintype "passive"))
      (node (ref "F1") (pin "5") (pinfunction "GND_5") (pintype "passive"))
      (node (ref "F1") (pin "6") (pinfunction "GND_6") (pintype "passive"))
      (node (ref "L5") (pin "2") (pinfunction "2_2") (pintype "passive"))
      (node (ref "P1") (pin "2") (pinfunction "Y_2") (pintype "passive"))
      (node (ref "P2") (pin "3") (pinfunction "3_3") (pintype "passive"))
      (node (ref "P2") (pin "5") (pinfunction "5_5") (pintype "passive"))
      (node (ref "P3") (pin "3") (pinfunction "GND_3") (pintype "power_in"))
      (node (ref "P3") (pin "6") (pinfunction "GND_6") (pintype "power_in"))
      (node (ref "P4") (pin "3") (pinfunction "GND_3") (pintype "power_in"))
      (node (ref "P4") (pin "6") (pinfunction "GND_6") (pintype "power_in"))
      (node (ref "Q1") (pin "1") (pinfunction "G_1") (pintype "passive"))
      (node (ref "R1") (pin "2") (pinfunction "2_2") (pintype "passive"))
      (node (ref "R16") (pin "2") (pinfunction "2_2") (pintype "passive"))
      (node (ref "R6") (pin "2") (pinfunction "2_2") (pintype "passive"))
      (node (ref "S1") (pin "2") (pinfunction "NO_2") (pintype "passive"))
      (node (ref "SW1") (pin "1") (pintype "passive"))
      (node (ref "SW1") (pin "2") (pintype "passive"))
      (node (ref "SW2") (pin "1") (pintype "passive"))
      (node (ref "SW2") (pin "2") (pintype "passive"))
      (node (ref "SW3") (pin "1") (pintype "passive"))
      (node (ref "SW3") (pin "2") (pintype "passive"))
      (node (ref "SW4") (pin "1") (pintype "passive"))
      (node (ref "SW4") (pin "2") (pintype "passive"))
      (node (ref "SW5") (pin "1") (pintype "passive"))
      (node (ref "SW5") (pin "2") (pintype "passive"))
      (node (ref "SW6") (pin "1") (pintype "passive"))
      (node (ref "SW6") (pin "2") (pintype "passive"))
      (node (ref "U1") (pin "2") (pinfunction "VSS_2") (pintype "passive"))
      (node (ref "U2") (pin "31") (pinfunction "VSS_31") (pintype "passive"))
      (node (ref "U2") (pin "4") (pinfunction "VSS_4") (pintype "passive"))
      (node (ref "U2") (pin "47") (pinfunction "VSS_47") (pintype "passive"))
      (node (ref "U3") (pin "1") (pinfunction "-_1") (pintype "passive"))
      (node (ref "U4") (pin "16") (pinfunction "GND_16") (pintype "passive"))
      (node (ref "U4") (pin "19") (pinfunction "GND_19") (pintype "passive"))
      (node (ref "U4") (pin "21") (pinfunction "PAD_21") (pintype "passive"))
      (node (ref "USB_1") (pin "5") (pinfunction "GND_5") (pintype "passive"))
      (node (ref "USB_1") (pin "6") (pinfunction "Shield_6") (pintype "passive"))
      (node (ref "USB_1") (pin "7") (pinfunction "Shield_7") (pintype "passive"))
      (node (ref "USB_1") (pin "8") (pinfunction "Shield_8") (pintype "passive"))
      (node (ref "USB_1") (pin "9") (pinfunction "Shield_9") (pintype "passive"))
      (node (ref "V1") (pin "1") (pinfunction "GND_1") (pintype "passive"))
      (node (ref "Y1") (pin "2") (pinfunction "GND_2") (pintype "passive"))
      (node (ref "Y1") (pin "4") (pinfunction "GND_4") (pintype "passive"))
      (node (ref "Y2") (pin "2") (pinfunction "GND_2") (pintype "passive"))
      (node (ref "Y2") (pin "4") (pinfunction "GND_4") (pintype "passive"))
    )
    (net (code "39") (name "Net-(D3-K)") (class "Default")
      (node (ref "D3") (pin "2") (pinfunction "K_2") (pintype "passive"))
      (node (ref "R6") (pin "1") (pinfunction "1_1") (pintype "passive"))
    )
    (net (code "40") (name "Net-(D4-B)") (class "Default")
      (node (ref "D4") (pin "3") (pinfunction "B_3") (pintype "passive"))
      (node (ref "R10") (pin "2") (pinfunction "2_2") (pintype "passive"))
    )
    (net (code "41") (name "Net-(D4-G)") (class "Default")
      (node (ref "D4") (pin "4") (pinfunction "G_4") (pintype "passive"))
      (node (ref "R8") (pin "2") (pinfunction "2_2") (pintype "passive"))
    )
    (net (code "42") (name "Net-(D4-R)") (class "Default")
      (node (ref "D4") (pin "1") (pinfunction "R_1") (pintype "passive"))
      (node (ref "R9") (pin "2") (pinfunction "2_2") (pintype "passive"))
    )
    (net (code "43") (name "Net-(F1-DC)") (class "Default")
      (node (ref "C1") (pin "1") (pinfunction "1_1") (pintype "passive"))
      (node (ref "F1") (pin "2") (pinfunction "DC_2") (pintype "passive"))
    )
    (net (code "44") (name "Net-(F1-UP)") (class "Default")
      (node (ref "C10") (pin "2") (pinfunction "2_2") (pintype "passive"))
      (node (ref "F1") (pin "1") (pinfunction "UP_1") (pintype "passive"))
      (node (ref "R14") (pin "2") (pinfunction "2_2") (pintype "passive"))
    )
    (net (code "45") (name "Net-(Q1-D)") (class "Default")
      (node (ref "C8") (pin "1") (pinfunction "1_1") (pintype "passive"))
      (node (ref "Q1") (pin "3") (pinfunction "D_3") (pintype "passive"))
      (node (ref "U3") (pin "2") (pinfunction "+_2") (pintype "passive"))
    )
    (net (code "46") (name "Net-(Q1-S)") (class "Default")
      (node (ref "C3") (pin "1") (pinfunction "1_1") (pintype "passive"))
      (node (ref "Q1") (pin "2") (pinfunction "S_2") (pintype "passive"))
      (node (ref "Q2") (pin "2") (pinfunction "S_2") (pintype "passive"))
      (node (ref "R2") (pin "2") (pinfunction "2_2") (pintype "passive"))
      (node (ref "U1") (pin "3") (pinfunction "VBAT_3") (pintype "passive"))
    )
    (net (code "47") (name "Net-(Q2-D)") (class "Default")
      (node (ref "Q2") (pin "3") (pinfunction "D_3") (pintype "passive"))
      (node (ref "Q3") (pin "2") (pinfunction "S_2") (pintype "passive"))
    )
    (net (code "48") (name "Net-(Q2-G)") (class "Default")
      (node (ref "Q2") (pin "1") (pinfunction "G_1") (pintype "passive"))
      (node (ref "R2") (pin "1") (pinfunction "1_1") (pintype "passive"))
      (node (ref "R5") (pin "2") (pinfunction "2_2") (pintype "passive"))
    )
    (net (code "49") (name "Net-(Q3-D)") (class "Default")
      (node (ref "Q3") (pin "3") (pinfunction "D_3") (pintype "passive"))
      (node (ref "Q4") (pin "3") (pinfunction "D_3") (pintype "passive"))
    )
    (net (code "50") (name "Net-(S1-COMMON)") (class "Default")
      (node (ref "R5") (pin "1") (pinfunction "1_1") (pintype "passive"))
      (node (ref "S1") (pin "1") (pinfunction "COMMON_1") (pintype "passive"))
    )
    (net (code "51") (name "Net-(U1-PROG)") (class "Default")
      (node (ref "R1") (pin "1") (pinfunction "1_1") (pintype "passive"))
      (node (ref "U1") (pin "5") (pinfunction "PROG_5") (pintype "passive"))
    )
    (net (code "52") (name "Net-(U2A-VDDA)") (class "Default")
      (node (ref "C23") (pin "2") (pinfunction "2_2") (pintype "passive"))
      (node (ref "C31") (pin "2") (pinfunction "2_2") (pintype "passive"))
      (node (ref "L2") (pin "1") (pinfunction "1_1") (pintype "passive"))
      (node (ref "U2") (pin "13") (pinfunction "VDDA_13") (pintype "passive"))
      (node (ref "U2") (pin "14") (pinfunction "VREFH_14") (pintype "passive"))
    )
    (net (code "53") (name "Net-(U2A-VREFL)") (class "Default")
      (node (ref "C23") (pin "1") (pinfunction "1_1") (pintype "passive"))
      (node (ref "C31") (pin "1") (pinfunction "1_1") (pintype "passive"))
      (node (ref "L5") (pin "1") (pinfunction "1_1") (pintype "passive"))
      (node (ref "U2") (pin "15") (pinfunction "VREFL_15") (pintype "passive"))
      (node (ref "U2") (pin "16") (pinfunction "VSSA_16") (pintype "passive"))
    )
    (net (code "54") (name "Net-(U4-DCOUPL)") (class "Default")
      (node (ref "C18") (pin "1") (pinfunction "1_1") (pintype "passive"))
      (node (ref "U4") (pin "5") (pinfunction "DCOUPL_5") (pintype "passive"))
    )
    (net (code "55") (name "Net-(U4-RBIAS)") (class "Default")
      (node (ref "R16") (pin "1") (pinfunction "1_1") (pintype "passive"))
      (node (ref "U4") (pin "17") (pinfunction "RBIAS_17") (pintype "passive"))
    )
    (net (code "56") (name "Net-(U4-XOSC_Q1)") (class "Default")
      (node (ref "C26") (pin "2") (pinfunction "2_2") (pintype "passive"))
      (node (ref "U4") (pin "8") (pinfunction "XOSC_Q1_8") (pintype "passive"))
      (node (ref "Y1") (pin "1") (pinfunction "X1_1") (pintype "passive"))
    )
    (net (code "57") (name "Net-(U4-XOSC_Q2)") (class "Default")
      (node (ref "C27") (pin "2") (pinfunction "2_2") (pintype "passive"))
      (node (ref "U4") (pin "10") (pinfunction "XOSC_Q2_10") (pintype "passive"))
      (node (ref "Y1") (pin "3") (pinfunction "X2_3") (pintype "passive"))
    )
    (net (code "58") (name "Net-(USB_1-VBUS)") (class "Default")
      (node (ref "L1") (pin "2") (pinfunction "2_2") (pintype "passive"))
      (node (ref "USB_1") (pin "1") (pinfunction "VBUS_1") (pintype "passive"))
    )
    (net (code "59") (name "Vreg") (class "Default")
      (node (ref "C4") (pin "1") (pinfunction "1_1") (pintype "passive"))
      (node (ref "C6") (pin "1") (pinfunction "1_1") (pintype "passive"))
      (node (ref "D1") (pin "3") (pinfunction "0_3") (pintype "passive"))
      (node (ref "Q4") (pin "2") (pinfunction "S_2") (pintype "passive"))
      (node (ref "V1") (pin "3") (pinfunction "Vin_3") (pintype "passive"))
    )
    (net (code "60") (name "unconnected-(D1-0-Pad2)") (class "Default")
      (node (ref "D1") (pin "2") (pinfunction "0_2") (pintype "passive"))
    )
    (net (code "61") (name "unconnected-(P2-Pad6)") (class "Default")
      (node (ref "P2") (pin "6") (pinfunction "6_6") (pintype "passive"))
    )
    (net (code "62") (name "unconnected-(P2-Pad7)") (class "Default")
      (node (ref "P2") (pin "7") (pinfunction "7_7") (pintype "passive"))
    )
    (net (code "63") (name "unconnected-(P2-Pad8)") (class "Default")
      (node (ref "P2") (pin "8") (pinfunction "8_8") (pintype "passive"))
    )
    (net (code "64") (name "unconnected-(P2-Pad9)") (class "Default")
      (node (ref "P2") (pin "9") (pinfunction "9_9") (pintype "passive"))
    )
    (net (code "65") (name "unconnected-(P5-Pad1)") (class "Default")
      (node (ref "P5") (pin "1") (pinfunction "1_1") (pintype "passive"))
    )
    (net (code "66") (name "unconnected-(P5-Pad2)") (class "Default")
      (node (ref "P5") (pin "2") (pinfunction "2_2") (pintype "passive"))
    )
    (net (code "67") (name "unconnected-(P5-Pad3)") (class "Default")
      (node (ref "P5") (pin "3") (pinfunction "3_3") (pintype "passive"))
    )
    (net (code "68") (name "unconnected-(P5-Pad4)") (class "Default")
      (node (ref "P5") (pin "4") (pinfunction "4_4") (pintype "passive"))
    )
    (net (code "69") (name "unconnected-(P6-Pad1)") (class "Default")
      (node (ref "P6") (pin "1") (pinfunction "1_1") (pintype "passive"))
    )
    (net (code "70") (name "unconnected-(P6-Pad2)") (class "Default")
      (node (ref "P6") (pin "2") (pinfunction "2_2") (pintype "passive"))
    )
    (net (code "71") (name "unconnected-(P6-Pad3)") (class "Default")
      (node (ref "P6") (pin "3") (pinfunction "3_3") (pintype "passive"))
    )
    (net (code "72") (name "unconnected-(P6-Pad4)") (class "Default")
      (node (ref "P6") (pin "4") (pinfunction "4_4") (pintype "passive"))
    )
    (net (code "73") (name "unconnected-(SW1-Pad4)") (class "Default")
      (node (ref "SW1") (pin "4") (pintype "passive"))
    )
    (net (code "74") (name "unconnected-(SW6-Pad4)") (class "Default")
      (node (ref "SW6") (pin "4") (pintype "passive"))
    )
    (net (code "75") (name "unconnected-(U2A-PTE1-Pad2)") (class "Default")
      (node (ref "U2") (pin "2") (pinfunction "PTE1_2") (pintype "passive"))
    )
    (net (code "76") (name "unconnected-(U2B-PTA1-Pad23)") (class "Default")
      (node (ref "U2") (pin "23") (pinfunction "PTA1_23") (pintype "passive"))
    )
    (net (code "77") (name "unconnected-(U2B-PTA2-Pad24)") (class "Default")
      (node (ref "U2") (pin "24") (pinfunction "PTA2_24") (pintype "passive"))
    )
    (net (code "78") (name "unconnected-(U2B-PTA4-Pad26)") (class "Default")
      (node (ref "U2") (pin "26") (pinfunction "PTA4_26") (pintype "passive"))
    )
    (net (code "79") (name "unconnected-(U2B-PTA5-Pad27)") (class "Default")
      (node (ref "U2") (pin "27") (pinfunction "PTA5_27") (pintype "passive"))
    )
    (net (code "80") (name "unconnected-(U2B-PTA12-Pad28)") (class "Default")
      (node (ref "U2") (pin "28") (pinfunction "PTA12_28") (pintype "passive"))
    )
    (net (code "81") (name "unconnected-(U2B-PTA13-Pad29)") (class "Default")
      (node (ref "U2") (pin "29") (pinfunction "PTA13_29") (pintype "passive"))
    )
    (net (code "82") (name "unconnected-(U2B-PTE24-Pad20)") (class "Default")
      (node (ref "U2") (pin "20") (pinfunction "PTE24_20") (pintype "passive"))
    )
    (net (code "83") (name "unconnected-(U2B-PTE25-Pad21)") (class "Default")
      (node (ref "U2") (pin "21") (pinfunction "PTE25_21") (pintype "passive"))
    )
    (net (code "84") (name "unconnected-(U2B-PTE29-Pad17)") (class "Default")
      (node (ref "U2") (pin "17") (pinfunction "PTE29_17") (pintype "passive"))
    )
    (net (code "85") (name "unconnected-(U2B-PTE30-Pad18)") (class "Default")
      (node (ref "U2") (pin "18") (pinfunction "PTE30_18") (pintype "passive"))
    )
    (net (code "86") (name "unconnected-(U2B-PTE31-Pad19)") (class "Default")
      (node (ref "U2") (pin "19") (pinfunction "PTE31_19") (pintype "passive"))
    )
    (net (code "87") (name "unconnected-(U2C-PTB0{slash}LLWU_P5-Pad35)") (class "Default")
      (node (ref "U2") (pin "35") (pinfunction "PTB0/LLWU_P5_35") (pintype "passive"))
    )
    (net (code "88") (name "unconnected-(U2C-PTB17-Pad40)") (class "Default")
      (node (ref "U2") (pin "40") (pinfunction "PTB17_40") (pintype "passive"))
    )
    (net (code "89") (name "unconnected-(U2C-PTB18-Pad41)") (class "Default")
      (node (ref "U2") (pin "41") (pinfunction "PTB18_41") (pintype "passive"))
    )
    (net (code "90") (name "unconnected-(U2C-PTB19-Pad42)") (class "Default")
      (node (ref "U2") (pin "42") (pinfunction "PTB19_42") (pintype "passive"))
    )
    (net (code "91") (name "unconnected-(U2C-PTC0-Pad43)") (class "Default")
      (node (ref "U2") (pin "43") (pinfunction "PTC0_43") (pintype "passive"))
    )
    (net (code "92") (name "unconnected-(U2C-PTC1{slash}LLWU_P6{slash}RTC_CLKIN-Pad44)") (class "Default")
      (node (ref "U2") (pin "44") (pinfunction "PTC1/LLWU_P6/RTC_CLKIN_44") (pintype "passive"))
    )
    (net (code "93") (name "unconnected-(U2C-PTC2-Pad45)") (class "Default")
      (node (ref "U2") (pin "45") (pinfunction "PTC2_45") (pintype "passive"))
    )
    (net (code "94") (name "unconnected-(U2C-PTC3{slash}LLWU_P7-Pad46)") (class "Default")
      (node (ref "U2") (pin "46") (pinfunction "PTC3/LLWU_P7_46") (pintype "passive"))
    )
    (net (code "95") (name "unconnected-(U2D-PTC4{slash}LLWU_P8-Pad49)") (class "Default")
      (node (ref "U2") (pin "49") (pinfunction "PTC4/LLWU_P8_49") (pintype "passive"))
    )
    (net (code "96") (name "unconnected-(U2D-PTC11-Pad56)") (class "Default")
      (node (ref "U2") (pin "56") (pinfunction "PTC11_56") (pintype "passive"))
    )
    (net (code "97") (name "unconnected-(U2D-PTD6{slash}LLWU_P15-Pad63)") (class "Default")
      (node (ref "U2") (pin "63") (pinfunction "PTD6/LLWU_P15_63") (pintype "passive"))
    )
    (net (code "98") (name "unconnected-(U2D-PTD7-Pad64)") (class "Default")
      (node (ref "U2") (pin "64") (pinfunction "PTD7_64") (pintype "passive"))
    )
    (net (code "99") (name "unconnected-(USB_1-NC-Pad4)") (class "Default")
      (node (ref "USB_1") (pin "4") (pinfunction "NC_4") (pintype "passive"))
    )
  )
)
